# Radio86RK-I2C.net
KiCad netlist of a schematic drawn in EAGLE
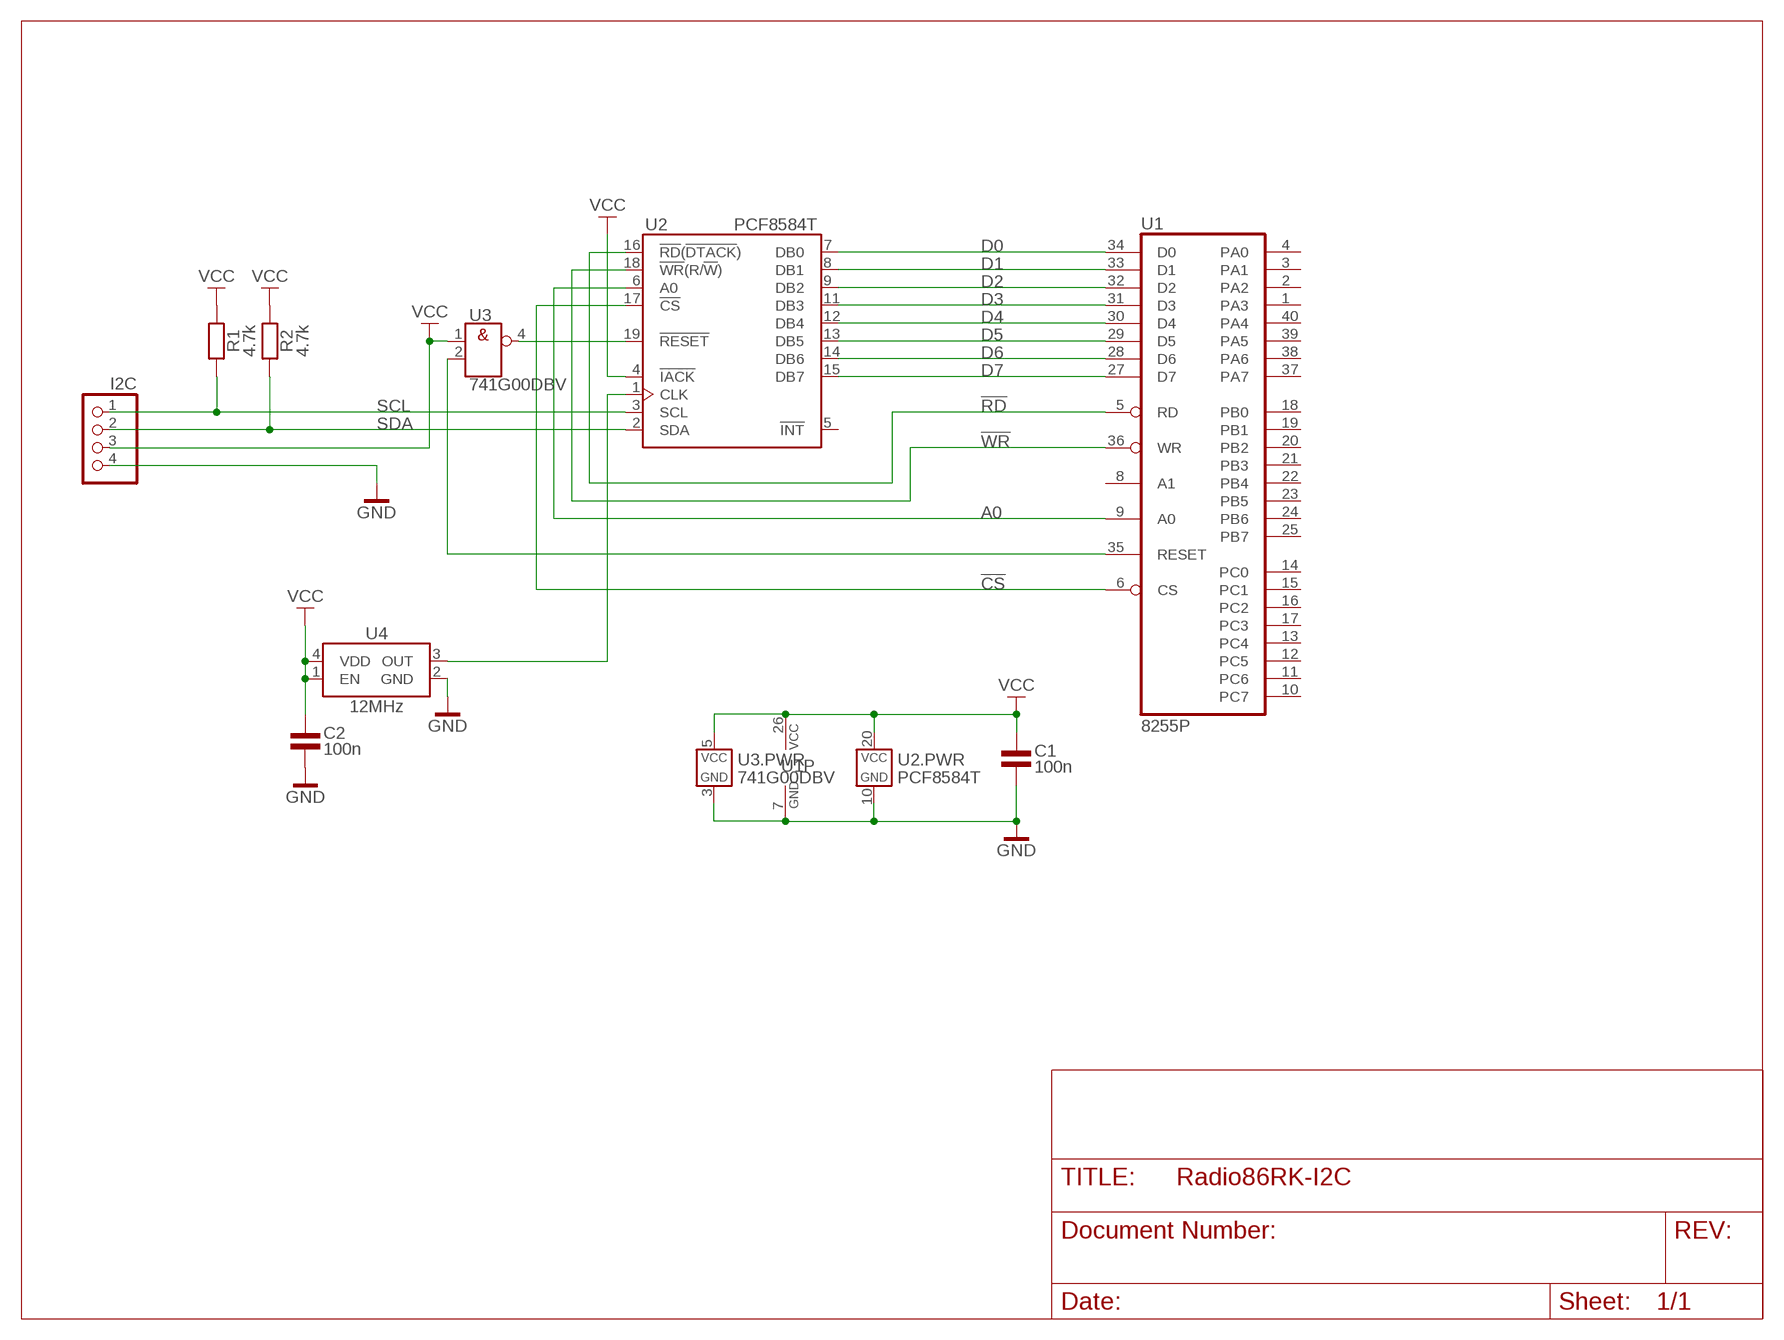
[diagram p0: schematic, sheet 1]

(export (version "E")
  (design (tool "Eeschema 10.0.6"))
  (components
    (comp (ref "C1")
      (value "100n")
      (footprint "eagle-import:0805@1")
      (libsource (lib "eagle-import") (part "CAPACITOR_SMD0805"))
    )
    (comp (ref "C2")
      (value "100n")
      (footprint "eagle-import:0805@1")
      (libsource (lib "eagle-import") (part "CAPACITOR_SMD0805"))
    )
    (comp (ref "I2C")
      (value "PINHD-1X4")
      (footprint "eagle-import:1X04")
      (libsource (lib "eagle-import") (part "PINHD-1X4"))
    )
    (comp (ref "R1")
      (value "4.7k")
      (footprint "eagle-import:0805")
      (libsource (lib "eagle-import") (part "RESISTOR0805"))
    )
    (comp (ref "R2")
      (value "4.7k")
      (footprint "eagle-import:0805")
      (libsource (lib "eagle-import") (part "RESISTOR0805"))
    )
    (comp (ref "U1")
      (value "8255P")
      (footprint "eagle-import:DIP40W")
      (libsource (lib "eagle-import") (part "8255P"))
    )
    (comp (ref "U2")
      (value "PCF8584T")
      (footprint "eagle-import:SO20W")
      (libsource (lib "eagle-import") (part "PCF8584T"))
    )
    (comp (ref "U3")
      (value "741G00DBV")
      (footprint "eagle-import:SOT23-5")
      (libsource (lib "eagle-import") (part "741G00DBV"))
    )
    (comp (ref "U4")
      (value "12MHz")
      (footprint "eagle-import:XT_5X7")
      (libsource (lib "eagle-import") (part "XT_5X7"))
    )
  )
  (nets
    (net (code "1") (name "/A0") (class "Default")
      (node (ref "U1") (pin "9") (pinfunction "A0_9") (pintype "input"))
      (node (ref "U2") (pin "6") (pinfunction "A0_6") (pintype "input"))
    )
    (net (code "2") (name "/D0") (class "Default")
      (node (ref "U1") (pin "34") (pinfunction "D0_34") (pintype "bidirectional"))
      (node (ref "U2") (pin "7") (pinfunction "DB0_7") (pintype "bidirectional"))
    )
    (net (code "3") (name "/D1") (class "Default")
      (node (ref "U1") (pin "33") (pinfunction "D1_33") (pintype "bidirectional"))
      (node (ref "U2") (pin "8") (pinfunction "DB1_8") (pintype "bidirectional"))
    )
    (net (code "4") (name "/D2") (class "Default")
      (node (ref "U1") (pin "32") (pinfunction "D2_32") (pintype "bidirectional"))
      (node (ref "U2") (pin "9") (pinfunction "DB2_9") (pintype "bidirectional"))
    )
    (net (code "5") (name "/D3") (class "Default")
      (node (ref "U1") (pin "31") (pinfunction "D3_31") (pintype "bidirectional"))
      (node (ref "U2") (pin "11") (pinfunction "DB3_11") (pintype "bidirectional"))
    )
    (net (code "6") (name "/D4") (class "Default")
      (node (ref "U1") (pin "30") (pinfunction "D4_30") (pintype "bidirectional"))
      (node (ref "U2") (pin "12") (pinfunction "DB4_12") (pintype "bidirectional"))
    )
    (net (code "7") (name "/D5") (class "Default")
      (node (ref "U1") (pin "29") (pinfunction "D5_29") (pintype "bidirectional"))
      (node (ref "U2") (pin "13") (pinfunction "DB5_13") (pintype "bidirectional"))
    )
    (net (code "8") (name "/D6") (class "Default")
      (node (ref "U1") (pin "28") (pinfunction "D6_28") (pintype "bidirectional"))
      (node (ref "U2") (pin "14") (pinfunction "DB6_14") (pintype "bidirectional"))
    )
    (net (code "9") (name "/D7") (class "Default")
      (node (ref "U1") (pin "27") (pinfunction "D7_27") (pintype "bidirectional"))
      (node (ref "U2") (pin "15") (pinfunction "DB7_15") (pintype "bidirectional"))
    )
    (net (code "10") (name "/SCL") (class "Default")
      (node (ref "I2C") (pin "1") (pinfunction "1_1") (pintype "passive"))
      (node (ref "R1") (pin "1") (pinfunction "P$1_1") (pintype "passive"))
      (node (ref "U2") (pin "3") (pinfunction "SCL_3") (pintype "open_collector"))
    )
    (net (code "11") (name "/SDA") (class "Default")
      (node (ref "I2C") (pin "2") (pinfunction "2_2") (pintype "passive"))
      (node (ref "R2") (pin "1") (pinfunction "P$1_1") (pintype "passive"))
      (node (ref "U2") (pin "2") (pinfunction "SDA_2") (pintype "open_collector"))
    )
    (net (code "12") (name "/~{CS}") (class "Default")
      (node (ref "U1") (pin "6") (pinfunction "CS_6") (pintype "input"))
      (node (ref "U2") (pin "17") (pinfunction "~{CS}_17") (pintype "input"))
    )
    (net (code "13") (name "/~{RD}") (class "Default")
      (node (ref "U1") (pin "5") (pinfunction "RD_5") (pintype "input"))
      (node (ref "U2") (pin "16") (pinfunction "~{RD}(~{DTACK})_16") (pintype "bidirectional"))
    )
    (net (code "14") (name "/~{WR}") (class "Default")
      (node (ref "U1") (pin "36") (pinfunction "WR_36") (pintype "input"))
      (node (ref "U2") (pin "18") (pinfunction "~{WR}(R/~{W})_18") (pintype "input"))
    )
    (net (code "15") (name "GND") (class "Default")
      (node (ref "C1") (pin "1") (pinfunction "P$1_1") (pintype "passive"))
      (node (ref "C2") (pin "1") (pinfunction "P$1_1") (pintype "passive"))
      (node (ref "I2C") (pin "4") (pinfunction "4_4") (pintype "passive"))
      (node (ref "U1") (pin "7") (pinfunction "GND_7") (pintype "power_in"))
      (node (ref "U2") (pin "10") (pinfunction "GND_10") (pintype "power_in"))
      (node (ref "U3") (pin "3") (pinfunction "GND_3") (pintype "power_in"))
      (node (ref "U4") (pin "2") (pinfunction "GND_2") (pintype "power_in"))
    )
    (net (code "16") (name "Net-(U1A-RESET)") (class "Default")
      (node (ref "U1") (pin "35") (pinfunction "RESET_35") (pintype "input"))
      (node (ref "U3") (pin "2") (pinfunction "B_2") (pintype "input"))
    )
    (net (code "17") (name "Net-(U2A-CLK)") (class "Default")
      (node (ref "U2") (pin "1") (pinfunction "CLK_1") (pintype "input"))
      (node (ref "U4") (pin "3") (pinfunction "OUT_3") (pintype "output"))
    )
    (net (code "18") (name "Net-(U2A-~{RESET})") (class "Default")
      (node (ref "U2") (pin "19") (pinfunction "~{RESET}_19") (pintype "bidirectional"))
      (node (ref "U3") (pin "4") (pinfunction "Y_4") (pintype "output"))
    )
    (net (code "19") (name "VCC") (class "Default")
      (node (ref "C1") (pin "2") (pinfunction "P$2_2") (pintype "passive"))
      (node (ref "C2") (pin "2") (pinfunction "P$2_2") (pintype "passive"))
      (node (ref "I2C") (pin "3") (pinfunction "3_3") (pintype "passive"))
      (node (ref "R1") (pin "2") (pinfunction "P$2_2") (pintype "passive"))
      (node (ref "R2") (pin "2") (pinfunction "P$2_2") (pintype "passive"))
      (node (ref "U1") (pin "26") (pinfunction "VCC_26") (pintype "power_in"))
      (node (ref "U2") (pin "20") (pinfunction "VCC_20") (pintype "power_in"))
      (node (ref "U2") (pin "4") (pinfunction "~{IACK}_4") (pintype "input"))
      (node (ref "U3") (pin "1") (pinfunction "A_1") (pintype "input"))
      (node (ref "U3") (pin "5") (pinfunction "VCC_5") (pintype "power_in"))
      (node (ref "U4") (pin "1") (pinfunction "EN_1") (pintype "input"))
      (node (ref "U4") (pin "4") (pinfunction "VDD_4") (pintype "power_in"))
    )
    (net (code "20") (name "unconnected-(U1A-A1-Pad8)") (class "Default")
      (node (ref "U1") (pin "8") (pinfunction "A1_8") (pintype "input"))
    )
    (net (code "21") (name "unconnected-(U1A-PA0-Pad4)") (class "Default")
      (node (ref "U1") (pin "4") (pinfunction "PA0_4") (pintype "bidirectional"))
    )
    (net (code "22") (name "unconnected-(U1A-PA1-Pad3)") (class "Default")
      (node (ref "U1") (pin "3") (pinfunction "PA1_3") (pintype "bidirectional"))
    )
    (net (code "23") (name "unconnected-(U1A-PA2-Pad2)") (class "Default")
      (node (ref "U1") (pin "2") (pinfunction "PA2_2") (pintype "bidirectional"))
    )
    (net (code "24") (name "unconnected-(U1A-PA3-Pad1)") (class "Default")
      (node (ref "U1") (pin "1") (pinfunction "PA3_1") (pintype "bidirectional"))
    )
    (net (code "25") (name "unconnected-(U1A-PA4-Pad40)") (class "Default")
      (node (ref "U1") (pin "40") (pinfunction "PA4_40") (pintype "bidirectional"))
    )
    (net (code "26") (name "unconnected-(U1A-PA5-Pad39)") (class "Default")
      (node (ref "U1") (pin "39") (pinfunction "PA5_39") (pintype "bidirectional"))
    )
    (net (code "27") (name "unconnected-(U1A-PA6-Pad38)") (class "Default")
      (node (ref "U1") (pin "38") (pinfunction "PA6_38") (pintype "bidirectional"))
    )
    (net (code "28") (name "unconnected-(U1A-PA7-Pad37)") (class "Default")
      (node (ref "U1") (pin "37") (pinfunction "PA7_37") (pintype "bidirectional"))
    )
    (net (code "29") (name "unconnected-(U1A-PB0-Pad18)") (class "Default")
      (node (ref "U1") (pin "18") (pinfunction "PB0_18") (pintype "bidirectional"))
    )
    (net (code "30") (name "unconnected-(U1A-PB1-Pad19)") (class "Default")
      (node (ref "U1") (pin "19") (pinfunction "PB1_19") (pintype "bidirectional"))
    )
    (net (code "31") (name "unconnected-(U1A-PB2-Pad20)") (class "Default")
      (node (ref "U1") (pin "20") (pinfunction "PB2_20") (pintype "bidirectional"))
    )
    (net (code "32") (name "unconnected-(U1A-PB3-Pad21)") (class "Default")
      (node (ref "U1") (pin "21") (pinfunction "PB3_21") (pintype "bidirectional"))
    )
    (net (code "33") (name "unconnected-(U1A-PB4-Pad22)") (class "Default")
      (node (ref "U1") (pin "22") (pinfunction "PB4_22") (pintype "bidirectional"))
    )
    (net (code "34") (name "unconnected-(U1A-PB5-Pad23)") (class "Default")
      (node (ref "U1") (pin "23") (pinfunction "PB5_23") (pintype "bidirectional"))
    )
    (net (code "35") (name "unconnected-(U1A-PB6-Pad24)") (class "Default")
      (node (ref "U1") (pin "24") (pinfunction "PB6_24") (pintype "bidirectional"))
    )
    (net (code "36") (name "unconnected-(U1A-PB7-Pad25)") (class "Default")
      (node (ref "U1") (pin "25") (pinfunction "PB7_25") (pintype "bidirectional"))
    )
    (net (code "37") (name "unconnected-(U1A-PC0-Pad14)") (class "Default")
      (node (ref "U1") (pin "14") (pinfunction "PC0_14") (pintype "bidirectional"))
    )
    (net (code "38") (name "unconnected-(U1A-PC1-Pad15)") (class "Default")
      (node (ref "U1") (pin "15") (pinfunction "PC1_15") (pintype "bidirectional"))
    )
    (net (code "39") (name "unconnected-(U1A-PC2-Pad16)") (class "Default")
      (node (ref "U1") (pin "16") (pinfunction "PC2_16") (pintype "bidirectional"))
    )
    (net (code "40") (name "unconnected-(U1A-PC3-Pad17)") (class "Default")
      (node (ref "U1") (pin "17") (pinfunction "PC3_17") (pintype "bidirectional"))
    )
    (net (code "41") (name "unconnected-(U1A-PC4-Pad13)") (class "Default")
      (node (ref "U1") (pin "13") (pinfunction "PC4_13") (pintype "bidirectional"))
    )
    (net (code "42") (name "unconnected-(U1A-PC5-Pad12)") (class "Default")
      (node (ref "U1") (pin "12") (pinfunction "PC5_12") (pintype "bidirectional"))
    )
    (net (code "43") (name "unconnected-(U1A-PC6-Pad11)") (class "Default")
      (node (ref "U1") (pin "11") (pinfunction "PC6_11") (pintype "bidirectional"))
    )
    (net (code "44") (name "unconnected-(U1A-PC7-Pad10)") (class "Default")
      (node (ref "U1") (pin "10") (pinfunction "PC7_10") (pintype "bidirectional"))
    )
    (net (code "45") (name "unconnected-(U2A-~{INT}-Pad5)") (class "Default")
      (node (ref "U2") (pin "5") (pinfunction "~{INT}_5") (pintype "output"))
    )
  )
)
